# charlieland0.net
KiCad netlist of a schematic drawn in EAGLE
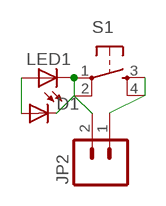
[diagram p0: schematic, sheet 1]

(export (version "E")
  (design (tool "Eeschema 10.0.6"))
  (components
    (comp (ref "D1")
      (value "DIODE1N4148")
      (footprint "eagle-import:DIODE-1N4148")
      (libsource (lib "eagle-import") (part "DIODE1N4148"))
    )
    (comp (ref "JP2")
      (value "M02")
      (footprint "eagle-import:1X02_LONGPADS")
      (libsource (lib "eagle-import") (part "M02"))
    )
    (comp (ref "LED1")
      (value "LED5MM")
      (footprint "eagle-import:LED5MM")
      (libsource (lib "eagle-import") (part "LED5MM"))
    )
    (comp (ref "S1")
      (value "TAC_SWITCHPTH")
      (footprint "eagle-import:TACTILE-PTH")
      (libsource (lib "eagle-import") (part "TAC_SWITCHPTH"))
    )
  )
  (nets
    (net (code "1") (name "Net-(D1-PadA)") (class "Default")
      (node (ref "D1") (pin "A") (pinfunction "A_A") (pintype "passive"))
      (node (ref "LED1") (pin "A") (pinfunction "A_A") (pintype "passive"))
    )
    (net (code "2") (name "Net-(JP2-Pad1)") (class "Default")
      (node (ref "JP2") (pin "1") (pinfunction "1_1") (pintype "passive"))
      (node (ref "S1") (pin "3") (pinfunction "3_3") (pintype "passive"))
      (node (ref "S1") (pin "4") (pinfunction "4_4") (pintype "passive"))
    )
    (net (code "3") (name "Net-(LED1-C)") (class "Default")
      (node (ref "D1") (pin "C") (pinfunction "C_C") (pintype "passive"))
      (node (ref "JP2") (pin "2") (pinfunction "2_2") (pintype "passive"))
      (node (ref "LED1") (pin "K") (pinfunction "C_K") (pintype "passive"))
      (node (ref "S1") (pin "1") (pinfunction "1_1") (pintype "passive"))
      (node (ref "S1") (pin "2") (pinfunction "2_2") (pintype "passive"))
    )
  )
)
